# power.net
KiCad netlist of a schematic drawn in Altium Designer
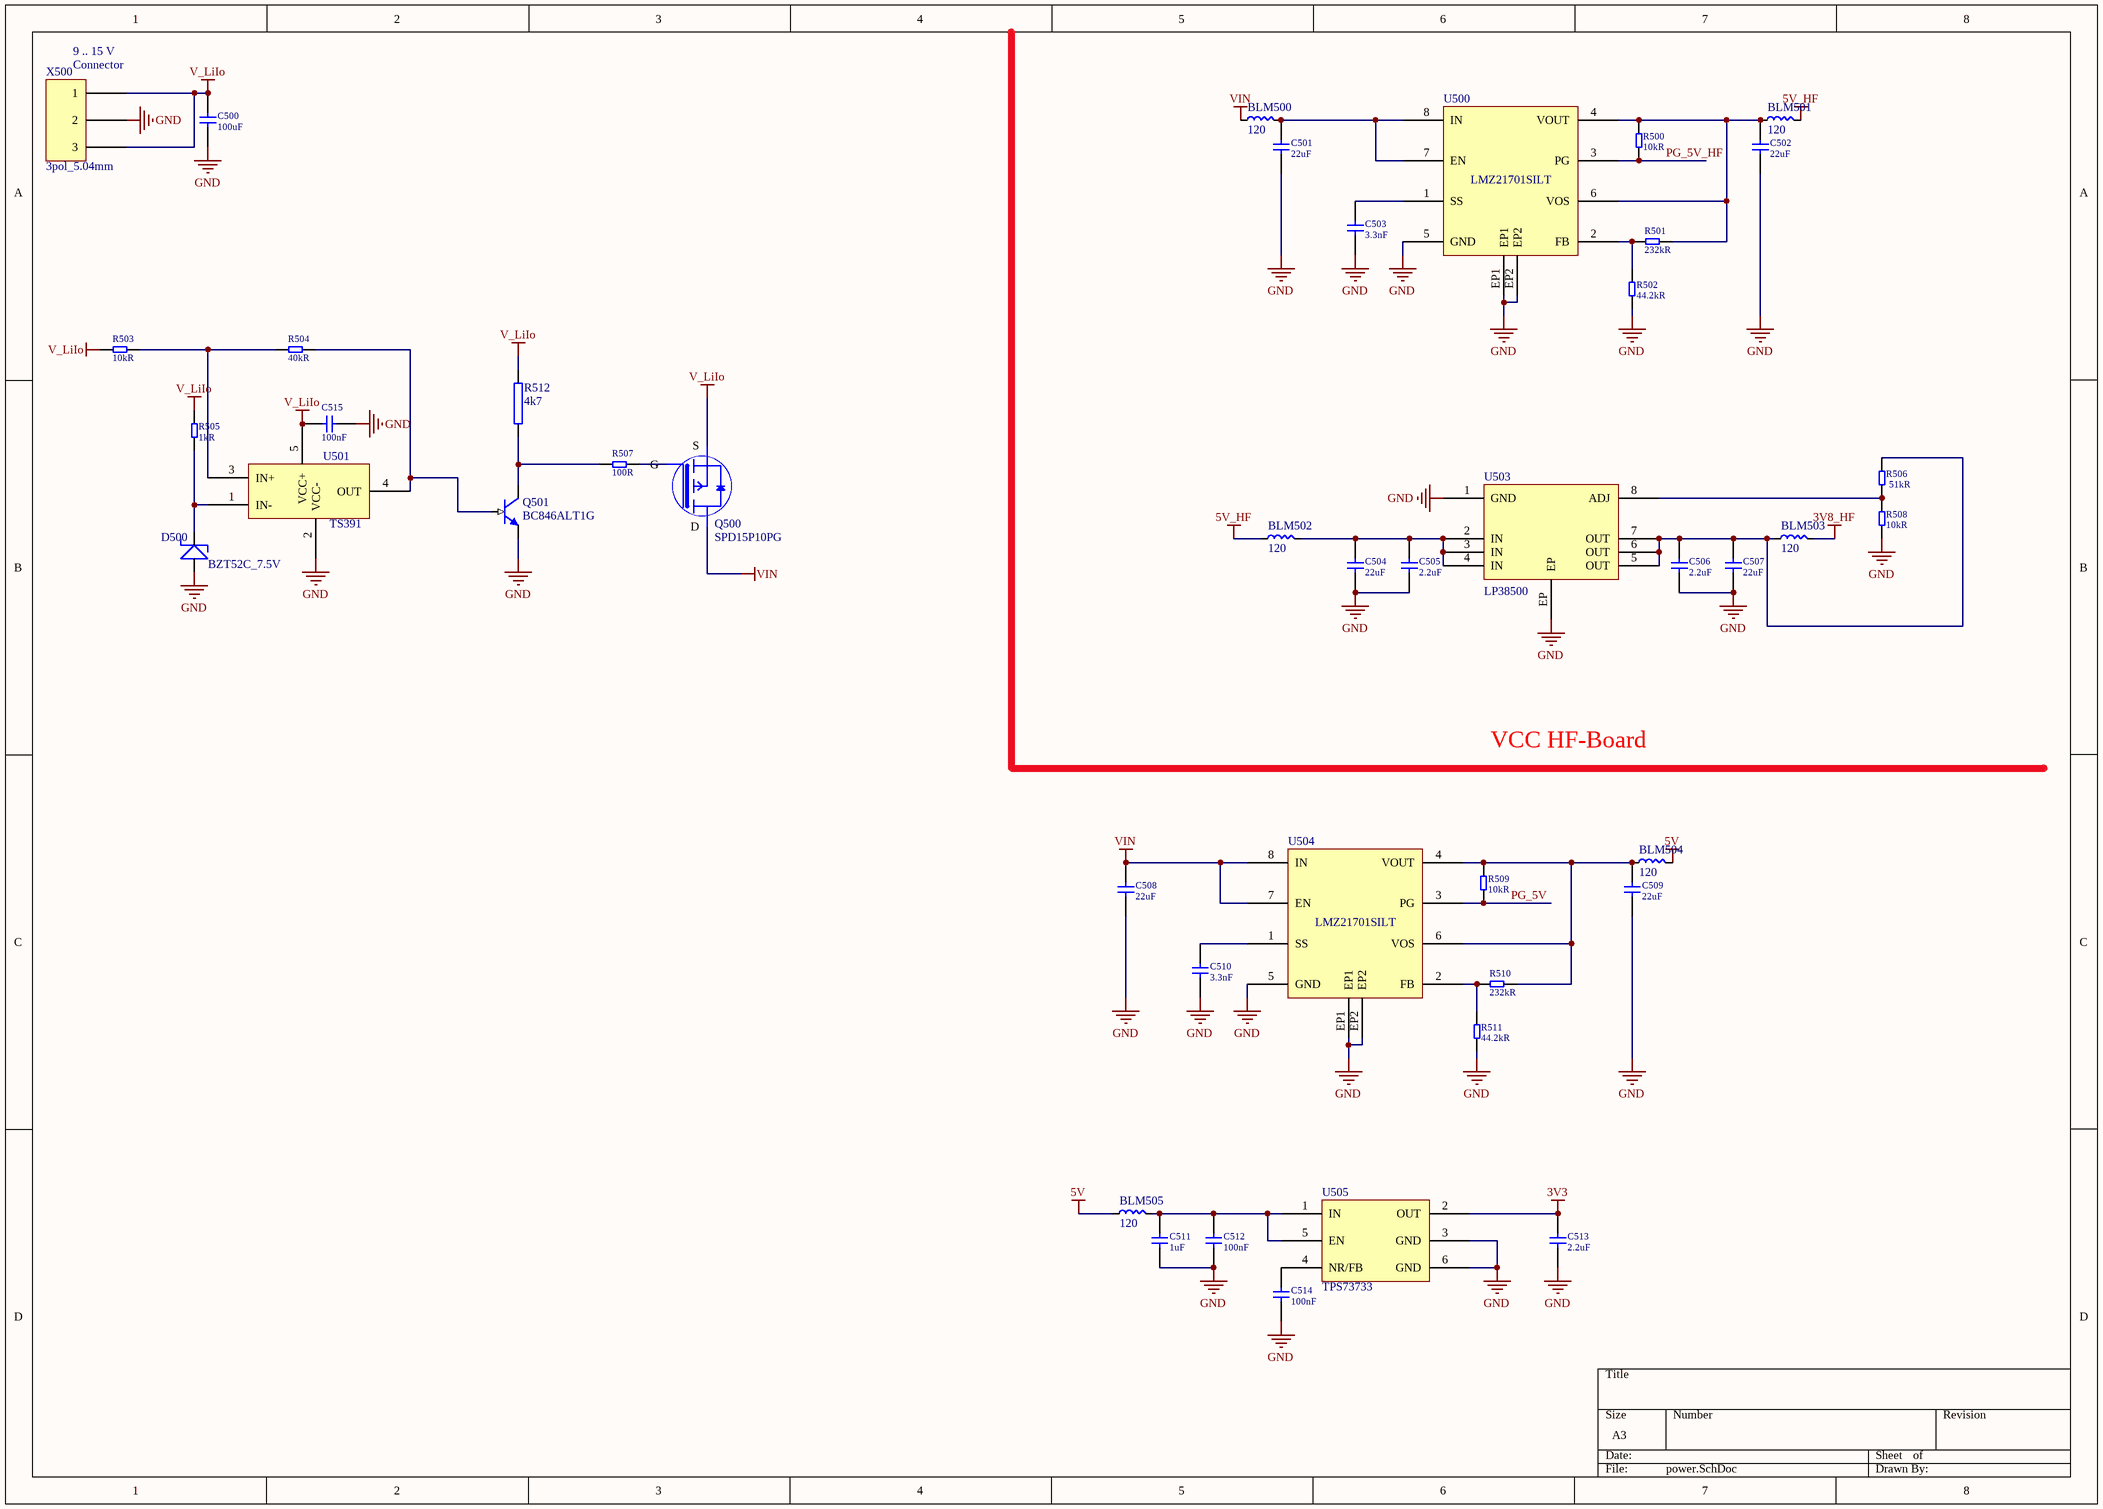
[diagram p0: power.SchDoc]

(export (version "E")
  (design (tool "Eeschema 10.0.6"))
  (components
    (comp (ref "BLM500")
      (value "FerriteBeat")
      (footprint "BLM18SG121TN1")
      (description "BLM18SG121TN1")
      (fields (field (name "ALTIUM_UNNAMED_1") "120"))
      (libsource (lib "zynq_board") (part "FerriteBeat"))
    )
    (comp (ref "BLM501")
      (value "FerriteBeat")
      (footprint "BLM18SG121TN1")
      (description "BLM18SG121TN1")
      (fields (field (name "ALTIUM_UNNAMED_1") "120"))
      (libsource (lib "zynq_board") (part "FerriteBeat"))
    )
    (comp (ref "BLM502")
      (value "FerriteBeat")
      (footprint "BLM18SG121TN1")
      (description "BLM18SG121TN1")
      (fields (field (name "ALTIUM_UNNAMED_1") "120"))
      (libsource (lib "zynq_board") (part "FerriteBeat"))
    )
    (comp (ref "BLM503")
      (value "FerriteBeat")
      (footprint "BLM18SG121TN1")
      (description "BLM18SG121TN1")
      (fields (field (name "ALTIUM_UNNAMED_1") "120"))
      (libsource (lib "zynq_board") (part "FerriteBeat"))
    )
    (comp (ref "BLM504")
      (value "FerriteBeat")
      (footprint "BLM18SG121TN1")
      (description "BLM18SG121TN1")
      (fields (field (name "ALTIUM_UNNAMED_1") "120"))
      (libsource (lib "zynq_board") (part "FerriteBeat"))
    )
    (comp (ref "BLM505")
      (value "FerriteBeat")
      (footprint "BLM18SG121TN1")
      (description "BLM18SG121TN1")
      (fields (field (name "ALTIUM_UNNAMED_1") "120"))
      (libsource (lib "zynq_board") (part "FerriteBeat"))
    )
    (comp (ref "C500")
      (value "100uF")
      (footprint "C_SMD_1210")
      (description "100uF, 1210, 25V, 20%, X5R")
      (fields (field (name "Comment") "SMD capacitor"))
      (libsource (lib "zynq_board") (part "C_SMD"))
    )
    (comp (ref "C501")
      (value "22uF")
      (footprint "C_SMD_0805")
      (description "22uF, 0805, 25V, 20%, X5R")
      (fields (field (name "Comment") "SMD capacitor"))
      (libsource (lib "zynq_board") (part "C_SMD"))
    )
    (comp (ref "C502")
      (value "22uF")
      (footprint "C_SMD_0805")
      (description "22uF, 0805, 10V, 20%, X5R")
      (fields (field (name "Comment") "SMD capacitor"))
      (libsource (lib "zynq_board") (part "C_SMD"))
    )
    (comp (ref "C503")
      (value "3.3nF")
      (footprint "C_SMD_0402")
      (description "3.3nF, 0402, 10V, 10%, X5R")
      (fields (field (name "Comment") "SMD capacitor"))
      (libsource (lib "zynq_board") (part "C_SMD"))
    )
    (comp (ref "C504")
      (value "22uF")
      (footprint "C_SMD_0805")
      (description "22uF, 0805, 10V, 20%, X5R")
      (fields (field (name "Comment") "SMD capacitor"))
      (libsource (lib "zynq_board") (part "C_SMD"))
    )
    (comp (ref "C505")
      (value "2.2uF")
      (footprint "C_SMD_0603")
      (description "2.2uF, 0603, 6.3V, 10%, X5R")
      (fields (field (name "Comment") "SMD capacitor"))
      (libsource (lib "zynq_board") (part "C_SMD"))
    )
    (comp (ref "C506")
      (value "2.2uF")
      (footprint "C_SMD_0603")
      (description "2.2uF, 0603, 6.3V, 10%, X5R")
      (libsource (lib "zynq_board") (part "C_SMD"))
    )
    (comp (ref "C507")
      (value "22uF")
      (footprint "C_SMD_0805")
      (description "22uF, 0805, 10V, 20%, X5R")
      (fields (field (name "Comment") "SMD capacitor"))
      (libsource (lib "zynq_board") (part "C_SMD"))
    )
    (comp (ref "C508")
      (value "22uF")
      (footprint "C_SMD_0805")
      (description "22uF, 0805, 25V, 20%, X5R")
      (fields (field (name "Comment") "SMD capacitor"))
      (libsource (lib "zynq_board") (part "C_SMD"))
    )
    (comp (ref "C509")
      (value "22uF")
      (footprint "C_SMD_0805")
      (description "22uF, 0805, 10V, 20%, X5R")
      (fields (field (name "Comment") "SMD capacitor"))
      (libsource (lib "zynq_board") (part "C_SMD"))
    )
    (comp (ref "C510")
      (value "3.3nF")
      (footprint "C_SMD_0402")
      (description "3.3nF, 0402, 10V, 10%, X5R")
      (fields (field (name "Comment") "SMD capacitor"))
      (libsource (lib "zynq_board") (part "C_SMD"))
    )
    (comp (ref "C511")
      (value "1uF")
      (footprint "C_SMD_0603")
      (description "1uF, 0603, 6.3V, 10%, X5R")
      (fields (field (name "Comment") "SMD capacitor"))
      (libsource (lib "zynq_board") (part "C_SMD"))
    )
    (comp (ref "C512")
      (value "100nF")
      (footprint "C_SMD_0402")
      (description "100nF, 0402, 6.3V, 10%, X5R")
      (fields (field (name "Comment") "SMD capacitor"))
      (libsource (lib "zynq_board") (part "C_SMD"))
    )
    (comp (ref "C513")
      (value "2.2uF")
      (footprint "C_SMD_0603")
      (description "2.2uF, 0603, 6.3V, 10%, X5R")
      (fields (field (name "Comment") "SMD capacitor"))
      (libsource (lib "zynq_board") (part "C_SMD"))
    )
    (comp (ref "C514")
      (value "100nF")
      (footprint "C_SMD_0402")
      (description "100nF, 0402, 6.3V, 10%, X5R")
      (fields (field (name "Comment") "SMD capacitor"))
      (libsource (lib "zynq_board") (part "C_SMD"))
    )
    (comp (ref "C515")
      (value "100nF")
      (footprint "C_SMD_0402")
      (description "100nF, 0402, 6.3V, 10%, X5R")
      (fields (field (name "Comment") "SMD capacitor"))
      (libsource (lib "zynq_board") (part "C_SMD"))
    )
    (comp (ref "D500")
      (value "BZT52C_7.5V")
      (footprint "SOD-323")
      (description "BZT52C7V5S-7-F")
      (libsource (lib "zynq_board") (part "BZT52C"))
    )
    (comp (ref "Q500")
      (value "SPD15P10PG")
      (footprint "PG-TO-252-3")
      (description "SPD15P10PGBTMA1, MOSFET P-CH 100V 15A TO252-3")
      (libsource (lib "zynq_board") (part "SPD15P10PG"))
    )
    (comp (ref "Q501")
      (value "BC846ALT1G")
      (footprint "SOT-23_BCE")
      (description "BC846A; Ic 100mA; Uce 65V; NPN Transistor")
      (fields
        (field (name "PART NUMBER") "npn-Transistor - BC846ALT1G")
        (field (name "SOURCE") "SN29500-3, Tab. 1")
      )
      (libsource (lib "Symeo_libs") (part "BJT_BCE"))
    )
    (comp (ref "R500")
      (value "10kR")
      (footprint "R_SMD_0402")
      (description "10kR, 0402, 1%")
      (fields (field (name "Comment") "SMD Resistor"))
      (libsource (lib "zynq_board") (part "R_SMD"))
    )
    (comp (ref "R501")
      (value "232kR")
      (footprint "R_SMD_0402")
      (description "232kR, 0402, 1%")
      (fields (field (name "Comment") "SMD Resistor"))
      (libsource (lib "zynq_board") (part "R_SMD"))
    )
    (comp (ref "R502")
      (value "44.2kR")
      (footprint "R_SMD_0402")
      (description "44.2kR, 0402, 1%")
      (fields (field (name "Comment") "SMD Resistor"))
      (libsource (lib "zynq_board") (part "R_SMD"))
    )
    (comp (ref "R503")
      (value "10kR")
      (footprint "R_SMD_0402")
      (description "10kR, 04020 ,1%")
      (fields (field (name "Comment") "SMD Resistor"))
      (libsource (lib "zynq_board") (part "R_SMD"))
    )
    (comp (ref "R504")
      (value "40kR")
      (footprint "R_SMD_0402")
      (description "40kR, 04020 ,1%")
      (fields (field (name "Comment") "SMD Resistor"))
      (libsource (lib "zynq_board") (part "R_SMD"))
    )
    (comp (ref "R505")
      (value "1kR")
      (footprint "R_SMD_0402")
      (description "1kR, 04020 ,1%")
      (fields (field (name "Comment") "SMD Resistor"))
      (libsource (lib "zynq_board") (part "R_SMD"))
    )
    (comp (ref "R506")
      (value "51kR")
      (footprint "R_SMD_0402")
      (description "43.2kR, 0402, 1%")
      (libsource (lib "zynq_board") (part "R_SMD"))
    )
    (comp (ref "R507")
      (value "100R")
      (footprint "R_SMD_0402")
      (description "100R, 04020 ,1%")
      (fields (field (name "Comment") "SMD Resistor"))
      (libsource (lib "zynq_board") (part "R_SMD"))
    )
    (comp (ref "R508")
      (value "10kR")
      (footprint "R_SMD_0402")
      (description "8.25kR, 0402, 1%")
      (libsource (lib "zynq_board") (part "R_SMD"))
    )
    (comp (ref "R509")
      (value "10kR")
      (footprint "R_SMD_0402")
      (description "10kR, 0402, 1%")
      (fields (field (name "Comment") "SMD Resistor"))
      (libsource (lib "zynq_board") (part "R_SMD"))
    )
    (comp (ref "R510")
      (value "232kR")
      (footprint "R_SMD_0402")
      (description "232kR, 0402, 1%")
      (fields (field (name "Comment") "SMD Resistor"))
      (libsource (lib "zynq_board") (part "R_SMD"))
    )
    (comp (ref "R511")
      (value "44.2kR")
      (footprint "R_SMD_0402")
      (description "44.2kR, 0402, 1%")
      (fields (field (name "Comment") "SMD Resistor"))
      (libsource (lib "zynq_board") (part "R_SMD"))
    )
    (comp (ref "R512")
      (value "4k7")
      (footprint "0402RN")
      (description "1%, 0.063W, 50V, 0402")
      (fields
        (field (name "PART NUMBER") "4k7, 0402, 1%, 0.063W, 50V")
        (field (name "SOURCE") "SN29500-4, Tabelle 2")
      )
      (libsource (lib "Symeo_libs") (part "_RES"))
    )
    (comp (ref "U500")
      (value "LMZ21701SILT")
      (footprint "LMZ21701")
      (libsource (lib "zynq_board") (part "LMZ21701"))
    )
    (comp (ref "U501")
      (value "TS391")
      (footprint "SOT-23-5")
      (description "TS391RILT,   Comparator General Purpose TTL, DTL, ECL, MOS, CMOS SOT-23-5")
      (libsource (lib "zynq_board") (part "TS391"))
    )
    (comp (ref "U503")
      (value "LP38500")
      (footprint "LP38500")
      (description "LP38502ASD-ADJ/NOPB")
      (libsource (lib "zynq_board") (part "LP38500"))
    )
    (comp (ref "U504")
      (value "LMZ21701SILT")
      (footprint "LMZ21701")
      (libsource (lib "zynq_board") (part "LMZ21701"))
    )
    (comp (ref "U505")
      (value "TPS73733")
      (footprint "SOT-223-6")
      (description "TPS73733DCQR")
      (libsource (lib "zynq_board") (part "TPS73733"))
    )
    (comp (ref "X500")
      (value "3pol_5.04mm")
      (footprint "POWER_CON")
      (description "3 polig, 5.04mm pitch")
      (libsource (lib "zynq_board") (part "CON_5.04_3pol"))
    )
  )
  (nets
    (net (code "1") (name "/PG_5V") (class "Default")
      (node (ref "R509") (pin "2") (pinfunction "2_2") (pintype "passive"))
      (node (ref "U504") (pin "3") (pinfunction "PG_3") (pintype "passive"))
    )
    (net (code "2") (name "/PG_5V_HF") (class "Default")
      (node (ref "R500") (pin "2") (pinfunction "2_2") (pintype "passive"))
      (node (ref "U500") (pin "3") (pinfunction "PG_3") (pintype "passive"))
    )
    (net (code "3") (name "3V3") (class "Default")
      (node (ref "C513") (pin "1") (pinfunction "1_1") (pintype "passive"))
      (node (ref "U505") (pin "2") (pinfunction "OUT_2") (pintype "passive"))
    )
    (net (code "4") (name "3V8_HF") (class "Default")
      (node (ref "BLM503") (pin "1") (pinfunction "1_1") (pintype "passive"))
    )
    (net (code "5") (name "5V") (class "Default")
      (node (ref "BLM504") (pin "1") (pinfunction "1_1") (pintype "passive"))
      (node (ref "BLM505") (pin "2") (pinfunction "2_2") (pintype "passive"))
    )
    (net (code "6") (name "5V_HF") (class "Default")
      (node (ref "BLM501") (pin "1") (pinfunction "1_1") (pintype "passive"))
      (node (ref "BLM502") (pin "2") (pinfunction "2_2") (pintype "passive"))
    )
    (net (code "7") (name "GND") (class "Default")
      (node (ref "C500") (pin "2") (pinfunction "2_2") (pintype "passive"))
      (node (ref "C501") (pin "2") (pinfunction "2_2") (pintype "passive"))
      (node (ref "C502") (pin "2") (pinfunction "2_2") (pintype "passive"))
      (node (ref "C503") (pin "2") (pinfunction "2_2") (pintype "passive"))
      (node (ref "C504") (pin "2") (pinfunction "2_2") (pintype "passive"))
      (node (ref "C505") (pin "2") (pinfunction "2_2") (pintype "passive"))
      (node (ref "C506") (pin "1") (pinfunction "1_1") (pintype "passive"))
      (node (ref "C507") (pin "1") (pinfunction "1_1") (pintype "passive"))
      (node (ref "C508") (pin "2") (pinfunction "2_2") (pintype "passive"))
      (node (ref "C509") (pin "2") (pinfunction "2_2") (pintype "passive"))
      (node (ref "C510") (pin "2") (pinfunction "2_2") (pintype "passive"))
      (node (ref "C511") (pin "2") (pinfunction "2_2") (pintype "passive"))
      (node (ref "C512") (pin "2") (pinfunction "2_2") (pintype "passive"))
      (node (ref "C513") (pin "2") (pinfunction "2_2") (pintype "passive"))
      (node (ref "C514") (pin "2") (pinfunction "2_2") (pintype "passive"))
      (node (ref "C515") (pin "2") (pinfunction "2_2") (pintype "passive"))
      (node (ref "D500") (pin "2") (pinfunction "2_2") (pintype "passive"))
      (node (ref "Q501") (pin "E") (pinfunction "E_E") (pintype "passive"))
      (node (ref "R502") (pin "2") (pinfunction "2_2") (pintype "passive"))
      (node (ref "R508") (pin "2") (pinfunction "2_2") (pintype "passive"))
      (node (ref "R511") (pin "2") (pinfunction "2_2") (pintype "passive"))
      (node (ref "U500") (pin "5") (pinfunction "GND_5") (pintype "passive"))
      (node (ref "U500") (pin "EP1") (pinfunction "EP1_EP1") (pintype "passive"))
      (node (ref "U500") (pin "EP2") (pinfunction "EP2_EP2") (pintype "passive"))
      (node (ref "U501") (pin "2") (pinfunction "VCC-_2") (pintype "passive"))
      (node (ref "U503") (pin "1") (pinfunction "GND_1") (pintype "passive"))
      (node (ref "U503") (pin "EP") (pinfunction "EP_EP") (pintype "passive"))
      (node (ref "U504") (pin "5") (pinfunction "GND_5") (pintype "passive"))
      (node (ref "U504") (pin "EP1") (pinfunction "EP1_EP1") (pintype "passive"))
      (node (ref "U504") (pin "EP2") (pinfunction "EP2_EP2") (pintype "passive"))
      (node (ref "U505") (pin "3") (pinfunction "GND_3") (pintype "passive"))
      (node (ref "U505") (pin "6") (pinfunction "GND_6") (pintype "passive"))
      (node (ref "X500") (pin "2") (pinfunction "2_2") (pintype "passive"))
    )
    (net (code "8") (name "Net-(BLM502-Pad1)") (class "Default")
      (node (ref "BLM502") (pin "1") (pinfunction "1_1") (pintype "passive"))
      (node (ref "C504") (pin "1") (pinfunction "1_1") (pintype "passive"))
      (node (ref "C505") (pin "1") (pinfunction "1_1") (pintype "passive"))
      (node (ref "U503") (pin "2") (pinfunction "IN_2") (pintype "passive"))
      (node (ref "U503") (pin "3") (pinfunction "IN_3") (pintype "passive"))
      (node (ref "U503") (pin "4") (pinfunction "IN_4") (pintype "passive"))
    )
    (net (code "9") (name "Net-(BLM503-Pad2)") (class "Default")
      (node (ref "BLM503") (pin "2") (pinfunction "2_2") (pintype "passive"))
      (node (ref "C506") (pin "2") (pinfunction "2_2") (pintype "passive"))
      (node (ref "C507") (pin "2") (pinfunction "2_2") (pintype "passive"))
      (node (ref "R506") (pin "1") (pinfunction "1_1") (pintype "passive"))
      (node (ref "U503") (pin "5") (pinfunction "OUT_5") (pintype "passive"))
      (node (ref "U503") (pin "6") (pinfunction "OUT_6") (pintype "passive"))
      (node (ref "U503") (pin "7") (pinfunction "OUT_7") (pintype "passive"))
    )
    (net (code "10") (name "Net-(Q500-G)") (class "Default")
      (node (ref "Q500") (pin "1") (pinfunction "G_1") (pintype "passive"))
      (node (ref "R507") (pin "1") (pinfunction "1_1") (pintype "passive"))
    )
    (net (code "11") (name "Net-(Q501-PadC)") (class "Default")
      (node (ref "Q501") (pin "C") (pinfunction "C_C") (pintype "passive"))
      (node (ref "R507") (pin "2") (pinfunction "2_2") (pintype "passive"))
      (node (ref "R512") (pin "1") (pintype "passive"))
    )
    (net (code "12") (name "Net-(U500-EN)") (class "Default")
      (node (ref "BLM500") (pin "1") (pinfunction "1_1") (pintype "passive"))
      (node (ref "C501") (pin "1") (pinfunction "1_1") (pintype "passive"))
      (node (ref "U500") (pin "7") (pinfunction "EN_7") (pintype "passive"))
      (node (ref "U500") (pin "8") (pinfunction "IN_8") (pintype "passive"))
    )
    (net (code "13") (name "Net-(U500-FB)") (class "Default")
      (node (ref "R501") (pin "1") (pinfunction "1_1") (pintype "passive"))
      (node (ref "R502") (pin "1") (pinfunction "1_1") (pintype "passive"))
      (node (ref "U500") (pin "2") (pinfunction "FB_2") (pintype "passive"))
    )
    (net (code "14") (name "Net-(U500-SS)") (class "Default")
      (node (ref "C503") (pin "1") (pinfunction "1_1") (pintype "passive"))
      (node (ref "U500") (pin "1") (pinfunction "SS_1") (pintype "passive"))
    )
    (net (code "15") (name "Net-(U500-VOS)") (class "Default")
      (node (ref "BLM501") (pin "2") (pinfunction "2_2") (pintype "passive"))
      (node (ref "C502") (pin "1") (pinfunction "1_1") (pintype "passive"))
      (node (ref "R500") (pin "1") (pinfunction "1_1") (pintype "passive"))
      (node (ref "R501") (pin "2") (pinfunction "2_2") (pintype "passive"))
      (node (ref "U500") (pin "4") (pinfunction "VOUT_4") (pintype "passive"))
      (node (ref "U500") (pin "6") (pinfunction "VOS_6") (pintype "passive"))
    )
    (net (code "16") (name "Net-(U501-IN+)") (class "Default")
      (node (ref "R503") (pin "2") (pinfunction "2_2") (pintype "passive"))
      (node (ref "R504") (pin "1") (pinfunction "1_1") (pintype "passive"))
      (node (ref "U501") (pin "3") (pinfunction "IN+_3") (pintype "passive"))
    )
    (net (code "17") (name "Net-(U501-IN-)") (class "Default")
      (node (ref "D500") (pin "1") (pinfunction "1_1") (pintype "passive"))
      (node (ref "R505") (pin "2") (pinfunction "2_2") (pintype "passive"))
      (node (ref "U501") (pin "1") (pinfunction "IN-_1") (pintype "passive"))
    )
    (net (code "18") (name "Net-(U501-OUT)") (class "Default")
      (node (ref "Q501") (pin "B") (pinfunction "B_B") (pintype "input"))
      (node (ref "R504") (pin "2") (pinfunction "2_2") (pintype "passive"))
      (node (ref "U501") (pin "4") (pinfunction "OUT_4") (pintype "passive"))
    )
    (net (code "19") (name "Net-(U503-ADJ)") (class "Default")
      (node (ref "R506") (pin "2") (pinfunction "2_2") (pintype "passive"))
      (node (ref "R508") (pin "1") (pinfunction "1_1") (pintype "passive"))
      (node (ref "U503") (pin "8") (pinfunction "ADJ_8") (pintype "passive"))
    )
    (net (code "20") (name "Net-(U504-FB)") (class "Default")
      (node (ref "R510") (pin "1") (pinfunction "1_1") (pintype "passive"))
      (node (ref "R511") (pin "1") (pinfunction "1_1") (pintype "passive"))
      (node (ref "U504") (pin "2") (pinfunction "FB_2") (pintype "passive"))
    )
    (net (code "21") (name "Net-(U504-SS)") (class "Default")
      (node (ref "C510") (pin "1") (pinfunction "1_1") (pintype "passive"))
      (node (ref "U504") (pin "1") (pinfunction "SS_1") (pintype "passive"))
    )
    (net (code "22") (name "Net-(U504-VOS)") (class "Default")
      (node (ref "BLM504") (pin "2") (pinfunction "2_2") (pintype "passive"))
      (node (ref "C509") (pin "1") (pinfunction "1_1") (pintype "passive"))
      (node (ref "R509") (pin "1") (pinfunction "1_1") (pintype "passive"))
      (node (ref "R510") (pin "2") (pinfunction "2_2") (pintype "passive"))
      (node (ref "U504") (pin "4") (pinfunction "VOUT_4") (pintype "passive"))
      (node (ref "U504") (pin "6") (pinfunction "VOS_6") (pintype "passive"))
    )
    (net (code "23") (name "Net-(U505-EN)") (class "Default")
      (node (ref "BLM505") (pin "1") (pinfunction "1_1") (pintype "passive"))
      (node (ref "C511") (pin "1") (pinfunction "1_1") (pintype "passive"))
      (node (ref "C512") (pin "1") (pinfunction "1_1") (pintype "passive"))
      (node (ref "U505") (pin "1") (pinfunction "IN_1") (pintype "passive"))
      (node (ref "U505") (pin "5") (pinfunction "EN_5") (pintype "passive"))
    )
    (net (code "24") (name "Net-(U505-NR{slash}FB)") (class "Default")
      (node (ref "C514") (pin "1") (pinfunction "1_1") (pintype "passive"))
      (node (ref "U505") (pin "4") (pinfunction "NR/FB_4") (pintype "passive"))
    )
    (net (code "25") (name "VIN") (class "Default")
      (node (ref "BLM500") (pin "2") (pinfunction "2_2") (pintype "passive"))
      (node (ref "C508") (pin "1") (pinfunction "1_1") (pintype "passive"))
      (node (ref "Q500") (pin "2") (pinfunction "D_2") (pintype "passive"))
      (node (ref "U504") (pin "7") (pinfunction "EN_7") (pintype "passive"))
      (node (ref "U504") (pin "8") (pinfunction "IN_8") (pintype "passive"))
    )
    (net (code "26") (name "V_LiIo") (class "Default")
      (node (ref "C500") (pin "1") (pinfunction "1_1") (pintype "passive"))
      (node (ref "C515") (pin "1") (pinfunction "1_1") (pintype "passive"))
      (node (ref "Q500") (pin "3") (pinfunction "S_3") (pintype "passive"))
      (node (ref "R503") (pin "1") (pinfunction "1_1") (pintype "passive"))
      (node (ref "R505") (pin "1") (pinfunction "1_1") (pintype "passive"))
      (node (ref "R512") (pin "2") (pintype "passive"))
      (node (ref "U501") (pin "5") (pinfunction "VCC+_5") (pintype "passive"))
      (node (ref "X500") (pin "1") (pinfunction "1_1") (pintype "passive"))
      (node (ref "X500") (pin "3") (pinfunction "3_3") (pintype "passive"))
    )
  )
)
